# windowV2.net
KiCad netlist of a schematic drawn in EAGLE
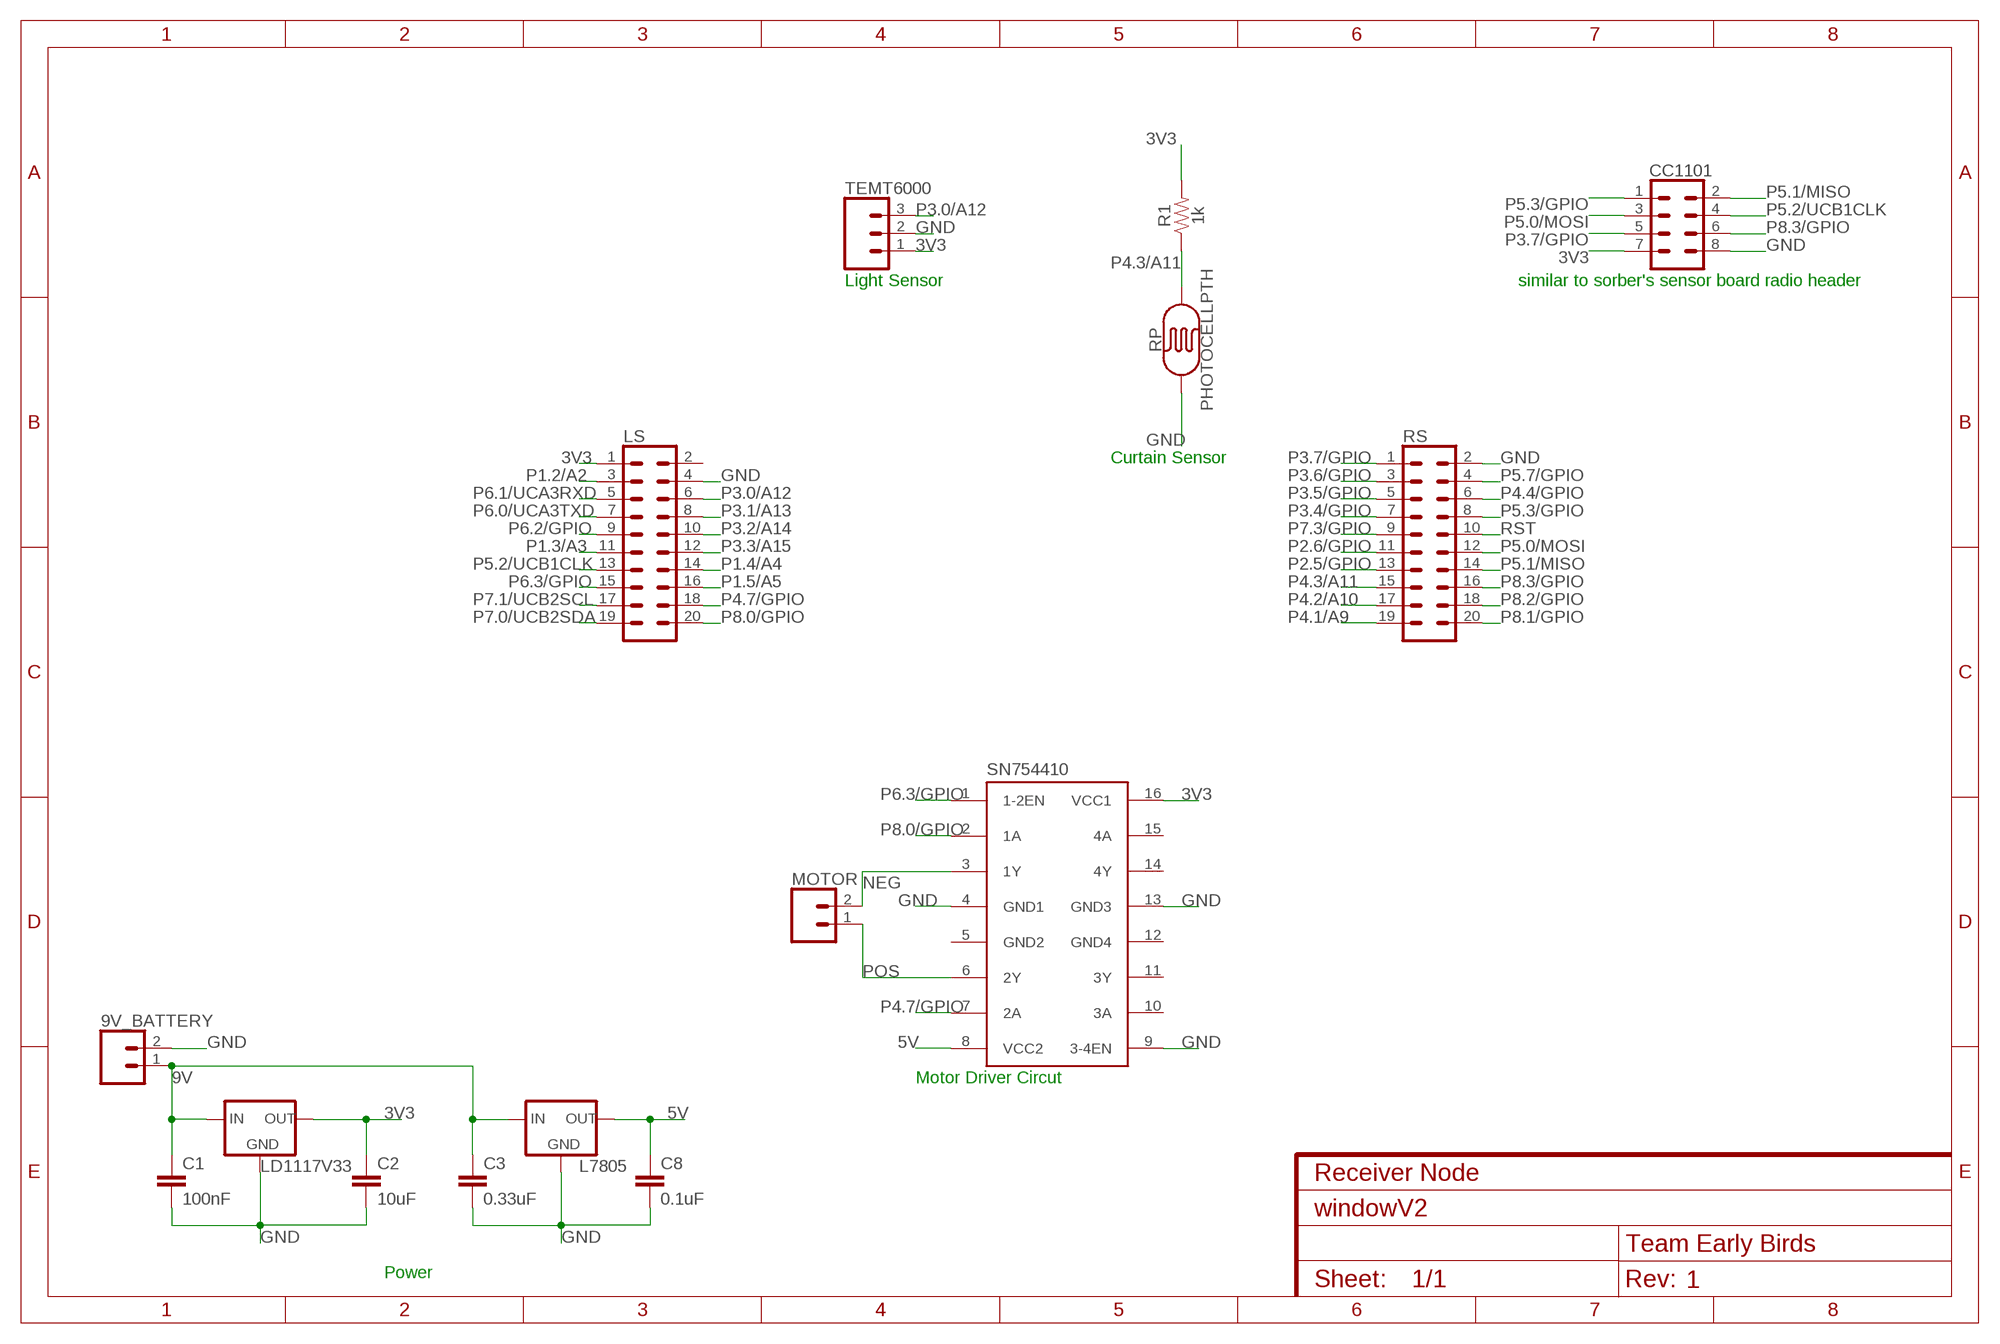
[diagram p0: schematic, sheet 1]

(export (version "E")
  (design (tool "Eeschema 10.0.6"))
  (components
    (comp (ref "9V_BATTERY")
      (value "CONN_02")
      (footprint "eagle-import:1X02")
      (libsource (lib "eagle-import") (part "CONN_02"))
    )
    (comp (ref "C1")
      (value "100nF")
      (footprint "eagle-import:C2.5-2")
      (libsource (lib "eagle-import") (part "C2.5/2"))
    )
    (comp (ref "C2")
      (value "10uF")
      (footprint "eagle-import:C2.5-2")
      (libsource (lib "eagle-import") (part "C2.5/2"))
    )
    (comp (ref "C3")
      (value "0.33uF")
      (footprint "eagle-import:C2.5-2")
      (libsource (lib "eagle-import") (part "C2.5/2"))
    )
    (comp (ref "C8")
      (value "0.1uF")
      (footprint "eagle-import:C2.5-2")
      (libsource (lib "eagle-import") (part "C2.5/2"))
    )
    (comp (ref "CC1101")
      (value "CONN_04X2")
      (footprint "eagle-import:2X4")
      (libsource (lib "eagle-import") (part "CONN_04X2"))
    )
    (comp (ref "L7805")
      (value "V_REG_78XX-TO-220")
      (footprint "eagle-import:TO-220-ALT")
      (libsource (lib "eagle-import") (part "V_REG_78XX-TO-220"))
    )
    (comp (ref "LD1117V33")
      (value "V_REG_LD1117VXX")
      (footprint "eagle-import:TO-220-ALT2")
      (libsource (lib "eagle-import") (part "V_REG_LD1117VXX"))
    )
    (comp (ref "LS")
      (value "CONN_10X2")
      (footprint "eagle-import:2X10")
      (libsource (lib "eagle-import") (part "CONN_10X2"))
    )
    (comp (ref "MOTOR")
      (value "CONN_02")
      (footprint "eagle-import:1X02")
      (libsource (lib "eagle-import") (part "CONN_02"))
    )
    (comp (ref "R1")
      (value "1k")
      (footprint "eagle-import:AXIAL-0.3")
      (libsource (lib "eagle-import") (part "1KOHM-HORIZ-1/4W-1%"))
    )
    (comp (ref "RP")
      (value "PHOTOCELLPTH")
      (footprint "eagle-import:PHOTOCELL")
      (libsource (lib "eagle-import") (part "PHOTOCELLPTH"))
    )
    (comp (ref "RS")
      (value "CONN_10X2")
      (footprint "eagle-import:2X10")
      (libsource (lib "eagle-import") (part "CONN_10X2"))
    )
    (comp (ref "SN754410")
      (value "L293D")
      (footprint "eagle-import:DIL16")
      (libsource (lib "eagle-import") (part "L293D"))
    )
    (comp (ref "TEMT6000")
      (value "455-1750-1-ND")
      (footprint "eagle-import:1X03")
      (libsource (lib "eagle-import") (part "CONN_03"))
    )
  )
  (nets
    (net (code "1") (name "/3V3") (class "Default")
      (node (ref "C2") (pin "1") (pinfunction "1_1") (pintype "passive"))
      (node (ref "CC1101") (pin "7") (pinfunction "7_7") (pintype "passive"))
      (node (ref "LD1117V33") (pin "OUT") (pinfunction "OUT_OUT") (pintype "passive"))
      (node (ref "LS") (pin "1") (pinfunction "1_1") (pintype "passive"))
      (node (ref "R1") (pin "P$2") (pinfunction "2_P$2") (pintype "passive"))
      (node (ref "SN754410") (pin "16") (pinfunction "VCC1_16") (pintype "power_in"))
      (node (ref "TEMT6000") (pin "1") (pinfunction "1_1") (pintype "passive"))
    )
    (net (code "2") (name "/5V") (class "Default")
      (node (ref "C8") (pin "1") (pinfunction "1_1") (pintype "passive"))
      (node (ref "L7805") (pin "OUT") (pinfunction "OUT_OUT") (pintype "passive"))
      (node (ref "SN754410") (pin "8") (pinfunction "VCC2_8") (pintype "power_in"))
    )
    (net (code "3") (name "/9V") (class "Default")
      (node (ref "9V_BATTERY") (pin "1") (pinfunction "1_1") (pintype "passive"))
      (node (ref "C1") (pin "1") (pinfunction "1_1") (pintype "passive"))
      (node (ref "C3") (pin "1") (pinfunction "1_1") (pintype "passive"))
      (node (ref "L7805") (pin "IN") (pinfunction "IN_IN") (pintype "input"))
      (node (ref "LD1117V33") (pin "IN") (pinfunction "IN_IN") (pintype "input"))
    )
    (net (code "4") (name "/GND") (class "Default")
      (node (ref "9V_BATTERY") (pin "2") (pinfunction "2_2") (pintype "passive"))
      (node (ref "C1") (pin "2") (pinfunction "2_2") (pintype "passive"))
      (node (ref "C2") (pin "2") (pinfunction "2_2") (pintype "passive"))
      (node (ref "C3") (pin "2") (pinfunction "2_2") (pintype "passive"))
      (node (ref "C8") (pin "2") (pinfunction "2_2") (pintype "passive"))
      (node (ref "CC1101") (pin "8") (pinfunction "8_8") (pintype "passive"))
      (node (ref "L7805") (pin "GND") (pinfunction "GND_GND") (pintype "input"))
      (node (ref "LD1117V33") (pin "GND") (pinfunction "GND_GND") (pintype "input"))
      (node (ref "LS") (pin "4") (pinfunction "4_4") (pintype "passive"))
      (node (ref "RP") (pin "1") (pinfunction "P$1_1") (pintype "bidirectional"))
      (node (ref "RS") (pin "2") (pinfunction "2_2") (pintype "passive"))
      (node (ref "SN754410") (pin "13") (pinfunction "GND3_13") (pintype "power_in"))
      (node (ref "SN754410") (pin "4") (pinfunction "GND1_4") (pintype "power_in"))
      (node (ref "SN754410") (pin "9") (pinfunction "3-4EN_9") (pintype "input"))
      (node (ref "TEMT6000") (pin "2") (pinfunction "2_2") (pintype "passive"))
    )
    (net (code "5") (name "/GND2") (class "Default")
      (node (ref "SN754410") (pin "5") (pinfunction "GND2_5") (pintype "power_in"))
    )
    (net (code "6") (name "/GND4") (class "Default")
      (node (ref "SN754410") (pin "12") (pinfunction "GND4_12") (pintype "power_in"))
    )
    (net (code "7") (name "/NEG") (class "Default")
      (node (ref "MOTOR") (pin "2") (pinfunction "2_2") (pintype "passive"))
      (node (ref "SN754410") (pin "3") (pinfunction "1Y_3") (pintype "output"))
    )
    (net (code "8") (name "/P1.2{slash}A2") (class "Default")
      (node (ref "LS") (pin "3") (pinfunction "3_3") (pintype "passive"))
    )
    (net (code "9") (name "/P1.3{slash}A3") (class "Default")
      (node (ref "LS") (pin "11") (pinfunction "11_11") (pintype "passive"))
    )
    (net (code "10") (name "/P1.4{slash}A4") (class "Default")
      (node (ref "LS") (pin "14") (pinfunction "14_14") (pintype "passive"))
    )
    (net (code "11") (name "/P1.5{slash}A5") (class "Default")
      (node (ref "LS") (pin "16") (pinfunction "16_16") (pintype "passive"))
    )
    (net (code "12") (name "/P2.5{slash}GPIO") (class "Default")
      (node (ref "RS") (pin "13") (pinfunction "13_13") (pintype "passive"))
    )
    (net (code "13") (name "/P2.6{slash}GPIO") (class "Default")
      (node (ref "RS") (pin "11") (pinfunction "11_11") (pintype "passive"))
    )
    (net (code "14") (name "/P3.0{slash}A12") (class "Default")
      (node (ref "LS") (pin "6") (pinfunction "6_6") (pintype "passive"))
      (node (ref "TEMT6000") (pin "3") (pinfunction "3_3") (pintype "passive"))
    )
    (net (code "15") (name "/P3.1{slash}A13") (class "Default")
      (node (ref "LS") (pin "8") (pinfunction "8_8") (pintype "passive"))
    )
    (net (code "16") (name "/P3.2{slash}A14") (class "Default")
      (node (ref "LS") (pin "10") (pinfunction "10_10") (pintype "passive"))
    )
    (net (code "17") (name "/P3.3{slash}A15") (class "Default")
      (node (ref "LS") (pin "12") (pinfunction "12_12") (pintype "passive"))
    )
    (net (code "18") (name "/P3.4{slash}GPIO") (class "Default")
      (node (ref "RS") (pin "7") (pinfunction "7_7") (pintype "passive"))
    )
    (net (code "19") (name "/P3.5{slash}GPIO") (class "Default")
      (node (ref "RS") (pin "5") (pinfunction "5_5") (pintype "passive"))
    )
    (net (code "20") (name "/P3.6{slash}GPIO") (class "Default")
      (node (ref "RS") (pin "3") (pinfunction "3_3") (pintype "passive"))
    )
    (net (code "21") (name "/P3.7{slash}GPIO") (class "Default")
      (node (ref "CC1101") (pin "5") (pinfunction "5_5") (pintype "passive"))
      (node (ref "RS") (pin "1") (pinfunction "1_1") (pintype "passive"))
    )
    (net (code "22") (name "/P4.1{slash}A9") (class "Default")
      (node (ref "RS") (pin "19") (pinfunction "19_19") (pintype "passive"))
    )
    (net (code "23") (name "/P4.2{slash}A10") (class "Default")
      (node (ref "RS") (pin "17") (pinfunction "17_17") (pintype "passive"))
    )
    (net (code "24") (name "/P4.3{slash}A11") (class "Default")
      (node (ref "R1") (pin "P$1") (pinfunction "1_P$1") (pintype "passive"))
      (node (ref "RP") (pin "2") (pinfunction "P$2_2") (pintype "bidirectional"))
      (node (ref "RS") (pin "15") (pinfunction "15_15") (pintype "passive"))
    )
    (net (code "25") (name "/P4.4{slash}GPIO") (class "Default")
      (node (ref "RS") (pin "6") (pinfunction "6_6") (pintype "passive"))
    )
    (net (code "26") (name "/P4.7{slash}GPIO") (class "Default")
      (node (ref "LS") (pin "18") (pinfunction "18_18") (pintype "passive"))
      (node (ref "SN754410") (pin "7") (pinfunction "2A_7") (pintype "input"))
    )
    (net (code "27") (name "/P5.0{slash}MOSI") (class "Default")
      (node (ref "CC1101") (pin "3") (pinfunction "3_3") (pintype "passive"))
      (node (ref "RS") (pin "12") (pinfunction "12_12") (pintype "passive"))
    )
    (net (code "28") (name "/P5.1{slash}MISO") (class "Default")
      (node (ref "CC1101") (pin "2") (pinfunction "2_2") (pintype "passive"))
      (node (ref "RS") (pin "14") (pinfunction "14_14") (pintype "passive"))
    )
    (net (code "29") (name "/P5.2{slash}UCB1CLK") (class "Default")
      (node (ref "CC1101") (pin "4") (pinfunction "4_4") (pintype "passive"))
      (node (ref "LS") (pin "13") (pinfunction "13_13") (pintype "passive"))
    )
    (net (code "30") (name "/P5.3{slash}GPIO") (class "Default")
      (node (ref "CC1101") (pin "1") (pinfunction "1_1") (pintype "passive"))
      (node (ref "RS") (pin "8") (pinfunction "8_8") (pintype "passive"))
    )
    (net (code "31") (name "/P5.7{slash}GPIO") (class "Default")
      (node (ref "RS") (pin "4") (pinfunction "4_4") (pintype "passive"))
    )
    (net (code "32") (name "/P6.0{slash}UCA3TXD") (class "Default")
      (node (ref "LS") (pin "7") (pinfunction "7_7") (pintype "passive"))
    )
    (net (code "33") (name "/P6.1{slash}UCA3RXD") (class "Default")
      (node (ref "LS") (pin "5") (pinfunction "5_5") (pintype "passive"))
    )
    (net (code "34") (name "/P6.2{slash}GPIO") (class "Default")
      (node (ref "LS") (pin "9") (pinfunction "9_9") (pintype "passive"))
    )
    (net (code "35") (name "/P6.3{slash}GPIO") (class "Default")
      (node (ref "LS") (pin "15") (pinfunction "15_15") (pintype "passive"))
      (node (ref "SN754410") (pin "1") (pinfunction "1-2EN_1") (pintype "input"))
    )
    (net (code "36") (name "/P7.0{slash}UCB2SDA") (class "Default")
      (node (ref "LS") (pin "19") (pinfunction "19_19") (pintype "passive"))
    )
    (net (code "37") (name "/P7.1{slash}UCB2SCL") (class "Default")
      (node (ref "LS") (pin "17") (pinfunction "17_17") (pintype "passive"))
    )
    (net (code "38") (name "/P7.3{slash}GPIO") (class "Default")
      (node (ref "RS") (pin "9") (pinfunction "9_9") (pintype "passive"))
    )
    (net (code "39") (name "/P8.0{slash}GPIO") (class "Default")
      (node (ref "LS") (pin "20") (pinfunction "20_20") (pintype "passive"))
      (node (ref "SN754410") (pin "2") (pinfunction "1A_2") (pintype "input"))
    )
    (net (code "40") (name "/P8.1{slash}GPIO") (class "Default")
      (node (ref "RS") (pin "20") (pinfunction "20_20") (pintype "passive"))
    )
    (net (code "41") (name "/P8.2{slash}GPIO") (class "Default")
      (node (ref "RS") (pin "18") (pinfunction "18_18") (pintype "passive"))
    )
    (net (code "42") (name "/P8.3{slash}GPIO") (class "Default")
      (node (ref "CC1101") (pin "6") (pinfunction "6_6") (pintype "passive"))
      (node (ref "RS") (pin "16") (pinfunction "16_16") (pintype "passive"))
    )
    (net (code "43") (name "/POS") (class "Default")
      (node (ref "MOTOR") (pin "1") (pinfunction "1_1") (pintype "passive"))
      (node (ref "SN754410") (pin "6") (pinfunction "2Y_6") (pintype "output"))
    )
    (net (code "44") (name "/RST") (class "Default")
      (node (ref "RS") (pin "10") (pinfunction "10_10") (pintype "passive"))
    )
    (net (code "45") (name "unconnected-(LS-Pad2)") (class "Default")
      (node (ref "LS") (pin "2") (pinfunction "2_2") (pintype "passive"))
    )
    (net (code "46") (name "unconnected-(SN754410-3A-Pad10)") (class "Default")
      (node (ref "SN754410") (pin "10") (pinfunction "3A_10") (pintype "input"))
    )
    (net (code "47") (name "unconnected-(SN754410-3Y-Pad11)") (class "Default")
      (node (ref "SN754410") (pin "11") (pinfunction "3Y_11") (pintype "output"))
    )
    (net (code "48") (name "unconnected-(SN754410-4A-Pad15)") (class "Default")
      (node (ref "SN754410") (pin "15") (pinfunction "4A_15") (pintype "input"))
    )
    (net (code "49") (name "unconnected-(SN754410-4Y-Pad14)") (class "Default")
      (node (ref "SN754410") (pin "14") (pinfunction "4Y_14") (pintype "output"))
    )
  )
)
